# ghettoduino.net
KiCad netlist of a schematic drawn in EAGLE
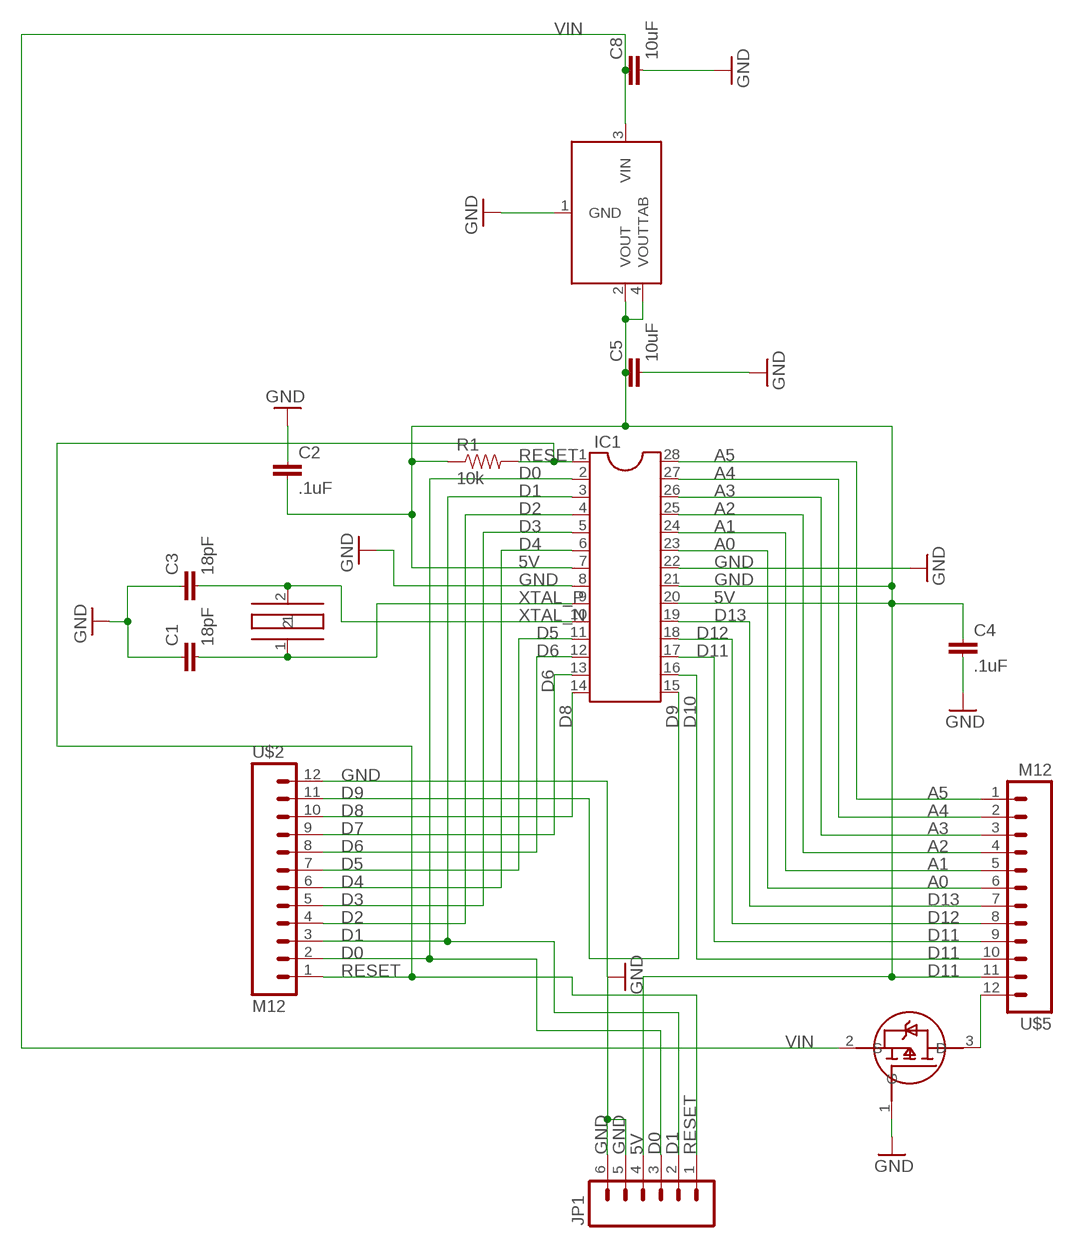
[diagram p0: schematic, sheet 1]

(export (version "E")
  (design (tool "Eeschema 10.0.6"))
  (components
    (comp (ref "5V")
      (value "5V-LDO-ZLDO1117")
      (footprint "eagle-import:ZLDO1117")
      (libsource (lib "eagle-import") (part "5V-LDO-ZLDO1117"))
    )
    (comp (ref "C1")
      (value "18pF")
      (footprint "eagle-import:0603-CAP")
      (libsource (lib "eagle-import") (part "CAP0603-CAP"))
    )
    (comp (ref "C2")
      (value ".1uF")
      (footprint "eagle-import:0805")
      (libsource (lib "eagle-import") (part "CAP0805"))
    )
    (comp (ref "C3")
      (value "18pF")
      (footprint "eagle-import:0603-CAP")
      (libsource (lib "eagle-import") (part "CAP0603-CAP"))
    )
    (comp (ref "C4")
      (value ".1uF")
      (footprint "eagle-import:0805")
      (libsource (lib "eagle-import") (part "CAP0805"))
    )
    (comp (ref "C5")
      (value "10uF")
      (footprint "eagle-import:1206")
      (libsource (lib "eagle-import") (part "CAP1206"))
    )
    (comp (ref "C8")
      (value "10uF")
      (footprint "eagle-import:1206")
      (libsource (lib "eagle-import") (part "CAP1206"))
    )
    (comp (ref "IC1")
      (value "DIL28-3")
      (footprint "eagle-import:DIL28-3")
      (libsource (lib "eagle-import") (part "DIL28-3"))
    )
    (comp (ref "JP1")
      (value "M06LOCK")
      (footprint "eagle-import:1X06_LOCK")
      (libsource (lib "eagle-import") (part "M06LOCK"))
    )
    (comp (ref "R1")
      (value "10k")
      (footprint "eagle-import:0805")
      (libsource (lib "eagle-import") (part "RESISTOR"))
    )
    (comp (ref "U$1")
      (value "HC49US")
      (footprint "eagle-import:HC49US")
      (libsource (lib "eagle-import") (part "HC49US"))
    )
    (comp (ref "U$2")
      (value "M12")
      (footprint "eagle-import:1X12_LOCK")
      (libsource (lib "eagle-import") (part "M12LOCK"))
    )
    (comp (ref "U$3")
      (value "P-MOSFET-PMV48XP")
      (footprint "eagle-import:SOT23-3LEAD")
      (libsource (lib "eagle-import") (part "P-MOSFET-PMV48XP"))
    )
    (comp (ref "U$5")
      (value "M12")
      (footprint "eagle-import:1X12_LOCK")
      (libsource (lib "eagle-import") (part "M12LOCK"))
    )
  )
  (nets
    (net (code "1") (name "/5V") (class "Default")
      (node (ref "5V") (pin "2") (pinfunction "VOUT_2") (pintype "bidirectional"))
      (node (ref "5V") (pin "4") (pinfunction "VOUTTAB_4") (pintype "bidirectional"))
      (node (ref "C2") (pin "2") (pinfunction "2_2") (pintype "passive"))
      (node (ref "C4") (pin "1") (pinfunction "1_1") (pintype "passive"))
      (node (ref "C5") (pin "1") (pinfunction "1_1") (pintype "passive"))
      (node (ref "IC1") (pin "20") (pinfunction "20_20") (pintype "passive"))
      (node (ref "IC1") (pin "21") (pinfunction "21_21") (pintype "passive"))
      (node (ref "IC1") (pin "7") (pinfunction "7_7") (pintype "passive"))
      (node (ref "JP1") (pin "4") (pinfunction "4_4") (pintype "passive"))
      (node (ref "R1") (pin "1") (pinfunction "1_1") (pintype "passive"))
      (node (ref "U$5") (pin "11") (pinfunction "11_11") (pintype "passive"))
    )
    (net (code "2") (name "/A0") (class "Default")
      (node (ref "IC1") (pin "23") (pinfunction "23_23") (pintype "passive"))
      (node (ref "U$5") (pin "6") (pinfunction "6_6") (pintype "passive"))
    )
    (net (code "3") (name "/A1") (class "Default")
      (node (ref "IC1") (pin "24") (pinfunction "24_24") (pintype "passive"))
      (node (ref "U$5") (pin "5") (pinfunction "5_5") (pintype "passive"))
    )
    (net (code "4") (name "/A2") (class "Default")
      (node (ref "IC1") (pin "25") (pinfunction "25_25") (pintype "passive"))
      (node (ref "U$5") (pin "4") (pinfunction "4_4") (pintype "passive"))
    )
    (net (code "5") (name "/A3") (class "Default")
      (node (ref "IC1") (pin "26") (pinfunction "26_26") (pintype "passive"))
      (node (ref "U$5") (pin "3") (pinfunction "3_3") (pintype "passive"))
    )
    (net (code "6") (name "/A4") (class "Default")
      (node (ref "IC1") (pin "27") (pinfunction "27_27") (pintype "passive"))
      (node (ref "U$5") (pin "2") (pinfunction "2_2") (pintype "passive"))
    )
    (net (code "7") (name "/A5") (class "Default")
      (node (ref "IC1") (pin "28") (pinfunction "28_28") (pintype "passive"))
      (node (ref "U$5") (pin "1") (pinfunction "1_1") (pintype "passive"))
    )
    (net (code "8") (name "/D0") (class "Default")
      (node (ref "IC1") (pin "2") (pinfunction "2_2") (pintype "passive"))
      (node (ref "JP1") (pin "3") (pinfunction "3_3") (pintype "passive"))
      (node (ref "U$2") (pin "2") (pinfunction "2_2") (pintype "passive"))
    )
    (net (code "9") (name "/D1") (class "Default")
      (node (ref "IC1") (pin "3") (pinfunction "3_3") (pintype "passive"))
      (node (ref "JP1") (pin "2") (pinfunction "2_2") (pintype "passive"))
      (node (ref "U$2") (pin "3") (pinfunction "3_3") (pintype "passive"))
    )
    (net (code "10") (name "/D2") (class "Default")
      (node (ref "IC1") (pin "4") (pinfunction "4_4") (pintype "passive"))
      (node (ref "U$2") (pin "4") (pinfunction "4_4") (pintype "passive"))
    )
    (net (code "11") (name "/D3") (class "Default")
      (node (ref "IC1") (pin "5") (pinfunction "5_5") (pintype "passive"))
      (node (ref "U$2") (pin "5") (pinfunction "5_5") (pintype "passive"))
    )
    (net (code "12") (name "/D4") (class "Default")
      (node (ref "IC1") (pin "6") (pinfunction "6_6") (pintype "passive"))
      (node (ref "U$2") (pin "6") (pinfunction "6_6") (pintype "passive"))
    )
    (net (code "13") (name "/D5") (class "Default")
      (node (ref "IC1") (pin "11") (pinfunction "11_11") (pintype "passive"))
      (node (ref "U$2") (pin "7") (pinfunction "7_7") (pintype "passive"))
    )
    (net (code "14") (name "/D6") (class "Default")
      (node (ref "IC1") (pin "12") (pinfunction "12_12") (pintype "passive"))
      (node (ref "U$2") (pin "8") (pinfunction "8_8") (pintype "passive"))
    )
    (net (code "15") (name "/D7") (class "Default")
      (node (ref "IC1") (pin "13") (pinfunction "13_13") (pintype "passive"))
      (node (ref "U$2") (pin "9") (pinfunction "9_9") (pintype "passive"))
    )
    (net (code "16") (name "/D8") (class "Default")
      (node (ref "IC1") (pin "14") (pinfunction "14_14") (pintype "passive"))
      (node (ref "U$2") (pin "10") (pinfunction "10_10") (pintype "passive"))
    )
    (net (code "17") (name "/D9") (class "Default")
      (node (ref "IC1") (pin "15") (pinfunction "15_15") (pintype "passive"))
      (node (ref "U$2") (pin "11") (pinfunction "11_11") (pintype "passive"))
    )
    (net (code "18") (name "/D10") (class "Default")
      (node (ref "IC1") (pin "16") (pinfunction "16_16") (pintype "passive"))
      (node (ref "U$5") (pin "10") (pinfunction "10_10") (pintype "passive"))
    )
    (net (code "19") (name "/D11") (class "Default")
      (node (ref "IC1") (pin "17") (pinfunction "17_17") (pintype "passive"))
      (node (ref "U$5") (pin "9") (pinfunction "9_9") (pintype "passive"))
    )
    (net (code "20") (name "/D12") (class "Default")
      (node (ref "IC1") (pin "18") (pinfunction "18_18") (pintype "passive"))
      (node (ref "U$5") (pin "8") (pinfunction "8_8") (pintype "passive"))
    )
    (net (code "21") (name "/D13") (class "Default")
      (node (ref "IC1") (pin "19") (pinfunction "19_19") (pintype "passive"))
      (node (ref "U$5") (pin "7") (pinfunction "7_7") (pintype "passive"))
    )
    (net (code "22") (name "/RESET") (class "Default")
      (node (ref "IC1") (pin "1") (pinfunction "1_1") (pintype "passive"))
      (node (ref "JP1") (pin "1") (pinfunction "1_1") (pintype "passive"))
      (node (ref "R1") (pin "2") (pinfunction "2_2") (pintype "passive"))
      (node (ref "U$2") (pin "1") (pinfunction "1_1") (pintype "passive"))
    )
    (net (code "23") (name "/VIN") (class "Default")
      (node (ref "5V") (pin "3") (pinfunction "VIN_3") (pintype "bidirectional"))
      (node (ref "C8") (pin "1") (pinfunction "1_1") (pintype "passive"))
      (node (ref "U$3") (pin "2") (pinfunction "S_2") (pintype "bidirectional"))
    )
    (net (code "24") (name "/XTAL_N") (class "Default")
      (node (ref "C3") (pin "2") (pinfunction "2_2") (pintype "passive"))
      (node (ref "IC1") (pin "10") (pinfunction "10_10") (pintype "passive"))
      (node (ref "U$1") (pin "2") (pinfunction "2_2") (pintype "bidirectional"))
    )
    (net (code "25") (name "/XTAL_P") (class "Default")
      (node (ref "C1") (pin "2") (pinfunction "2_2") (pintype "passive"))
      (node (ref "IC1") (pin "9") (pinfunction "9_9") (pintype "passive"))
      (node (ref "U$1") (pin "1") (pinfunction "1_1") (pintype "bidirectional"))
    )
    (net (code "26") (name "GND") (class "Default")
      (node (ref "5V") (pin "1") (pinfunction "GND_1") (pintype "bidirectional"))
      (node (ref "C1") (pin "1") (pinfunction "1_1") (pintype "passive"))
      (node (ref "C2") (pin "1") (pinfunction "1_1") (pintype "passive"))
      (node (ref "C3") (pin "1") (pinfunction "1_1") (pintype "passive"))
      (node (ref "C4") (pin "2") (pinfunction "2_2") (pintype "passive"))
      (node (ref "C5") (pin "2") (pinfunction "2_2") (pintype "passive"))
      (node (ref "C8") (pin "2") (pinfunction "2_2") (pintype "passive"))
      (node (ref "IC1") (pin "22") (pinfunction "22_22") (pintype "passive"))
      (node (ref "IC1") (pin "8") (pinfunction "8_8") (pintype "passive"))
      (node (ref "JP1") (pin "5") (pinfunction "5_5") (pintype "passive"))
      (node (ref "JP1") (pin "6") (pinfunction "6_6") (pintype "passive"))
      (node (ref "U$2") (pin "12") (pinfunction "12_12") (pintype "passive"))
      (node (ref "U$3") (pin "1") (pinfunction "G_1") (pintype "bidirectional"))
    )
    (net (code "27") (name "Net-(U$3-D)") (class "Default")
      (node (ref "U$3") (pin "3") (pinfunction "D_3") (pintype "bidirectional"))
      (node (ref "U$5") (pin "12") (pinfunction "12_12") (pintype "passive"))
    )
  )
)
